# Bipolar_Offset_Shifter.net
KiCad netlist of a schematic drawn in Altium Designer
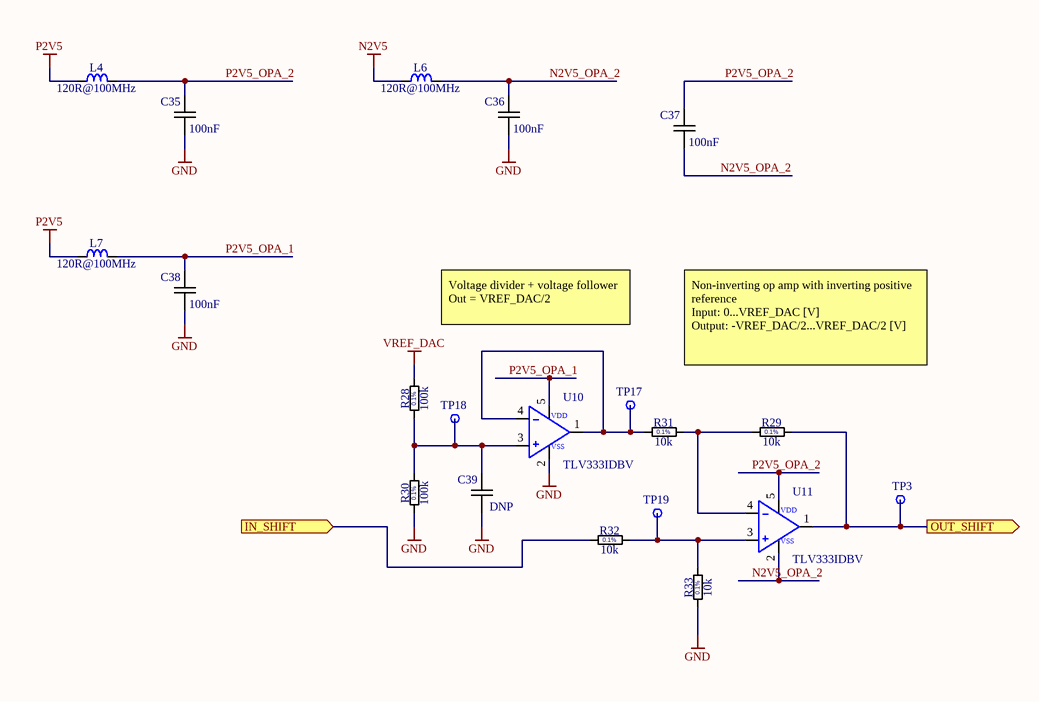
[diagram p0: Bipolar_Offset_Shifter.SchDoc]

(export (version "E")
  (design (tool "Eeschema 10.0.6"))
  (components
    (comp (ref "C35")
      (value "100nF")
      (footprint "CAPC0603X90N")
      (description "Non-polarised capacitor")
      (fields (field (name "MANUFACTURER PART NUMBER") "VJ0603Y104KXJCW1BC"))
      (libsource (lib "Capacitors") (part "Capacitor - non polarized"))
    )
    (comp (ref "C36")
      (value "100nF")
      (footprint "CAPC0603X90N")
      (description "Non-polarised capacitor")
      (fields (field (name "MANUFACTURER PART NUMBER") "VJ0603Y104KXJCW1BC"))
      (libsource (lib "Capacitors") (part "Capacitor - non polarized"))
    )
    (comp (ref "C37")
      (value "100nF")
      (footprint "CAPC0603X90N")
      (description "Non-polarised capacitor")
      (fields (field (name "MANUFACTURER PART NUMBER") "VJ0603Y104KXJCW1BC"))
      (libsource (lib "Capacitors") (part "Capacitor - non polarized"))
    )
    (comp (ref "C38")
      (value "100nF")
      (footprint "CAPC0603X90N")
      (description "Non-polarised capacitor")
      (fields (field (name "MANUFACTURER PART NUMBER") "VJ0603Y104KXJCW1BC"))
      (libsource (lib "Capacitors") (part "Capacitor - non polarized"))
    )
    (comp (ref "C39")
      (value "DNP")
      (footprint "CAPC0603X90N")
      (description "Non-polarised capacitor")
      (fields (field (name "MANUFACTURER PART NUMBER") "UNDEFINED"))
      (libsource (lib "Capacitors") (part "Capacitor - non polarized"))
    )
    (comp (ref "L4")
      (value "120R@100MHz")
      (footprint "INDC0603X90N")
      (description "Ferrite Bead")
      (fields (field (name "MANUFACTURER PART NUMBER") "BLM18PG121SN1D") (field (name "TOLERANCE") "25%"))
      (libsource (lib "Inductors") (part "Inductor"))
    )
    (comp (ref "L6")
      (value "120R@100MHz")
      (footprint "INDC0603X90N")
      (description "Ferrite Bead")
      (fields (field (name "MANUFACTURER PART NUMBER") "BLM18PG121SN1D") (field (name "TOLERANCE") "25%"))
      (libsource (lib "Inductors") (part "Inductor"))
    )
    (comp (ref "L7")
      (value "120R@100MHz")
      (footprint "INDC0603X90N")
      (description "Ferrite Bead")
      (fields (field (name "MANUFACTURER PART NUMBER") "BLM18PG121SN1D") (field (name "TOLERANCE") "25%"))
      (libsource (lib "Inductors") (part "Inductor"))
    )
    (comp (ref "R28")
      (value "100k")
      (footprint "RESC0603X60N")
      (description "General Purpose Thick Film Chip Resistor")
      (fields (field (name "MANUFACTURER PART NUMBER") "RT0603BRD07100KL") (field (name "TOLERANCE") "0.10%"))
      (libsource (lib "Resistors") (part "Resistor - 0.1%"))
    )
    (comp (ref "R29")
      (value "10k")
      (footprint "RESC0603X60N")
      (description "General Purpose Thick Film Chip Resistor")
      (fields (field (name "MANUFACTURER PART NUMBER") "RT0603BRD0710KL") (field (name "TOLERANCE") "0.10%"))
      (libsource (lib "Resistors") (part "Resistor - 0.1%"))
    )
    (comp (ref "R30")
      (value "100k")
      (footprint "RESC0603X60N")
      (description "General Purpose Thick Film Chip Resistor")
      (fields (field (name "MANUFACTURER PART NUMBER") "RT0603BRD07100KL") (field (name "TOLERANCE") "0.10%"))
      (libsource (lib "Resistors") (part "Resistor - 0.1%"))
    )
    (comp (ref "R31")
      (value "10k")
      (footprint "RESC0603X60N")
      (description "General Purpose Thick Film Chip Resistor")
      (fields (field (name "MANUFACTURER PART NUMBER") "RT0603BRD0710KL") (field (name "TOLERANCE") "0.10%"))
      (libsource (lib "Resistors") (part "Resistor - 0.1%"))
    )
    (comp (ref "R32")
      (value "10k")
      (footprint "RESC0603X60N")
      (description "General Purpose Thick Film Chip Resistor")
      (fields (field (name "MANUFACTURER PART NUMBER") "RT0603BRD0710KL") (field (name "TOLERANCE") "0.10%"))
      (libsource (lib "Resistors") (part "Resistor - 0.1%"))
    )
    (comp (ref "R33")
      (value "10k")
      (footprint "RESC0603X60N")
      (description "General Purpose Thick Film Chip Resistor")
      (fields (field (name "MANUFACTURER PART NUMBER") "RT0603BRD0710KL") (field (name "TOLERANCE") "0.10%"))
      (libsource (lib "Resistors") (part "Resistor - 0.1%"))
    )
    (comp (ref "TP3")
      (value "TestPoint")
      (footprint "TESTPOINT_SMD_C1P27MM")
      (description "1.27mm diameter SMD Test Point Area")
      (libsource (lib "Mechanical_and_PCB_Features") (part "Test Point"))
    )
    (comp (ref "TP17")
      (value "TestPoint")
      (footprint "TESTPOINT_SMD_C1P27MM")
      (description "1.27mm diameter SMD Test Point Area")
      (libsource (lib "Mechanical_and_PCB_Features") (part "Test Point"))
    )
    (comp (ref "TP18")
      (value "TestPoint")
      (footprint "TESTPOINT_SMD_C1P27MM")
      (description "1.27mm diameter SMD Test Point Area")
      (libsource (lib "Mechanical_and_PCB_Features") (part "Test Point"))
    )
    (comp (ref "TP19")
      (value "TestPoint")
      (footprint "TESTPOINT_SMD_C1P27MM")
      (description "1.27mm diameter SMD Test Point Area")
      (libsource (lib "Mechanical_and_PCB_Features") (part "Test Point"))
    )
    (comp (ref "U10")
      (value "TLV333IDBV")
      (footprint "SOT23-5")
      (libsource (lib "ICs_and_Semiconductors") (part "TLV333IDBV"))
    )
    (comp (ref "U11")
      (value "TLV333IDBV")
      (footprint "SOT23-5")
      (libsource (lib "ICs_and_Semiconductors") (part "TLV333IDBV"))
    )
  )
  (nets
    (net (code "1") (name "/IN_SHIFT") (class "Default")
      (node (ref "R32") (pin "1") (pinfunction "1_1") (pintype "passive"))
    )
    (net (code "2") (name "/N2V5_OPA_2") (class "Default")
      (node (ref "C36") (pin "1") (pinfunction "1_1") (pintype "passive"))
      (node (ref "C37") (pin "2") (pinfunction "2_2") (pintype "passive"))
      (node (ref "L6") (pin "2") (pinfunction "2_2") (pintype "passive"))
      (node (ref "U11") (pin "2") (pinfunction "VSS_2") (pintype "power_in"))
    )
    (net (code "3") (name "/OUT_SHIFT") (class "Default")
      (node (ref "R29") (pin "2") (pinfunction "2_2") (pintype "passive"))
      (node (ref "TP3") (pin "1") (pinfunction "1_1") (pintype "passive"))
      (node (ref "U11") (pin "1") (pinfunction "1_1") (pintype "passive"))
    )
    (net (code "4") (name "/P2V5_OPA_1") (class "Default")
      (node (ref "C38") (pin "1") (pinfunction "1_1") (pintype "passive"))
      (node (ref "L7") (pin "2") (pinfunction "2_2") (pintype "passive"))
      (node (ref "U10") (pin "5") (pinfunction "VDD_5") (pintype "power_in"))
    )
    (net (code "5") (name "/P2V5_OPA_2") (class "Default")
      (node (ref "C35") (pin "1") (pinfunction "1_1") (pintype "passive"))
      (node (ref "C37") (pin "1") (pinfunction "1_1") (pintype "passive"))
      (node (ref "L4") (pin "2") (pinfunction "2_2") (pintype "passive"))
      (node (ref "U11") (pin "5") (pinfunction "VDD_5") (pintype "power_in"))
    )
    (net (code "6") (name "GND") (class "Default")
      (node (ref "C35") (pin "2") (pinfunction "2_2") (pintype "passive"))
      (node (ref "C36") (pin "2") (pinfunction "2_2") (pintype "passive"))
      (node (ref "C38") (pin "2") (pinfunction "2_2") (pintype "passive"))
      (node (ref "C39") (pin "2") (pinfunction "2_2") (pintype "passive"))
      (node (ref "R30") (pin "1") (pinfunction "1_1") (pintype "passive"))
      (node (ref "R33") (pin "1") (pinfunction "1_1") (pintype "passive"))
      (node (ref "U10") (pin "2") (pinfunction "VSS_2") (pintype "power_in"))
    )
    (net (code "7") (name "N2V5") (class "Default")
      (node (ref "L6") (pin "1") (pinfunction "1_1") (pintype "passive"))
    )
    (net (code "8") (name "Net-(C39-Pad1)") (class "Default")
      (node (ref "C39") (pin "1") (pinfunction "1_1") (pintype "passive"))
      (node (ref "R28") (pin "1") (pinfunction "1_1") (pintype "passive"))
      (node (ref "R30") (pin "2") (pinfunction "2_2") (pintype "passive"))
      (node (ref "TP18") (pin "1") (pinfunction "1_1") (pintype "passive"))
      (node (ref "U10") (pin "3") (pinfunction "3_3") (pintype "passive"))
    )
    (net (code "9") (name "Net-(R29-Pad1)") (class "Default")
      (node (ref "R29") (pin "1") (pinfunction "1_1") (pintype "passive"))
      (node (ref "R31") (pin "2") (pinfunction "2_2") (pintype "passive"))
      (node (ref "U11") (pin "4") (pinfunction "4_4") (pintype "passive"))
    )
    (net (code "10") (name "Net-(R31-Pad1)") (class "Default")
      (node (ref "R31") (pin "1") (pinfunction "1_1") (pintype "passive"))
      (node (ref "TP17") (pin "1") (pinfunction "1_1") (pintype "passive"))
      (node (ref "U10") (pin "1") (pinfunction "1_1") (pintype "passive"))
      (node (ref "U10") (pin "4") (pinfunction "4_4") (pintype "passive"))
    )
    (net (code "11") (name "Net-(R32-Pad2)") (class "Default")
      (node (ref "R32") (pin "2") (pinfunction "2_2") (pintype "passive"))
      (node (ref "R33") (pin "2") (pinfunction "2_2") (pintype "passive"))
      (node (ref "TP19") (pin "1") (pinfunction "1_1") (pintype "passive"))
      (node (ref "U11") (pin "3") (pinfunction "3_3") (pintype "passive"))
    )
    (net (code "12") (name "P2V5") (class "Default")
      (node (ref "L4") (pin "1") (pinfunction "1_1") (pintype "passive"))
      (node (ref "L7") (pin "1") (pinfunction "1_1") (pintype "passive"))
    )
    (net (code "13") (name "VREF_DAC") (class "Default")
      (node (ref "R28") (pin "2") (pinfunction "2_2") (pintype "passive"))
    )
  )
)
